# isoSPI.net
KiCad netlist of a schematic drawn in Altium Designer
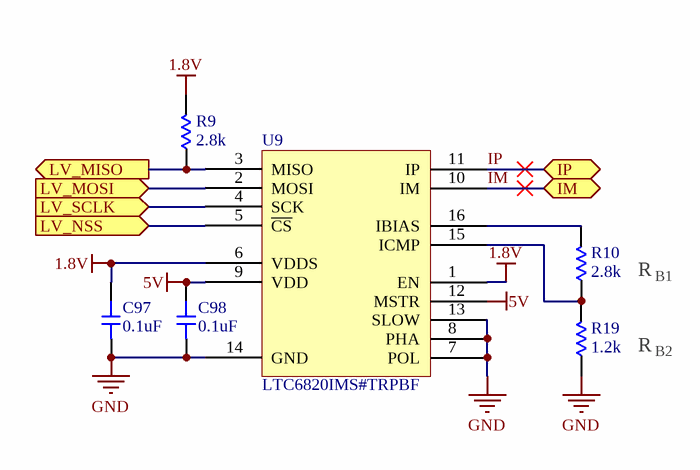
[diagram p0: isoSPI.SchDoc]

(export (version "E")
  (design (tool "Eeschema 10.0.6"))
  (components
    (comp (ref "C97")
      (value "0.1uF")
      (footprint "0603-CAP")
      (description "Capacitor")
      (libsource (lib "AMDC") (part "Capacitor"))
    )
    (comp (ref "C98")
      (value "0.1uF")
      (footprint "0603-CAP")
      (description "Capacitor")
      (libsource (lib "AMDC") (part "Capacitor"))
    )
    (comp (ref "R9")
      (value "2.8k")
      (footprint "0603-RES")
      (description "Resistor")
      (libsource (lib "AMDC") (part "Resistor"))
    )
    (comp (ref "R10")
      (value "2.8k")
      (footprint "0603-RES")
      (description "Resistor")
      (libsource (lib "AMDC") (part "Resistor"))
    )
    (comp (ref "R19")
      (value "1.2k")
      (footprint "0603-RES")
      (description "Resistor")
      (libsource (lib "AMDC") (part "Resistor"))
    )
    (comp (ref "U9")
      (value "LTC6820IMS#TRPBF")
      (footprint "TSSOP50P490X110-16N")
      (description "IC INTERFACE SPECIALIZED 16MSOP")
      (libsource (lib "AMDC") (part "LTC6820IMS#TRPBF"))
    )
  )
  (nets
    (net (code "1") (name "/IM") (class "Default")
      (node (ref "U9") (pin "10") (pinfunction "IM_10") (pintype "passive"))
    )
    (net (code "2") (name "/IP") (class "Default")
      (node (ref "U9") (pin "11") (pinfunction "IP_11") (pintype "passive"))
    )
    (net (code "3") (name "/LV_MISO") (class "Default")
      (node (ref "R9") (pin "1") (pinfunction "1_1") (pintype "passive"))
      (node (ref "U9") (pin "3") (pinfunction "MISO_3") (pintype "passive"))
    )
    (net (code "4") (name "/LV_MOSI") (class "Default")
      (node (ref "U9") (pin "2") (pinfunction "MOSI_2") (pintype "passive"))
    )
    (net (code "5") (name "/LV_NSS") (class "Default")
      (node (ref "U9") (pin "5") (pinfunction "~{CS}_5") (pintype "passive"))
    )
    (net (code "6") (name "/LV_SCLK") (class "Default")
      (node (ref "U9") (pin "4") (pinfunction "SCK_4") (pintype "passive"))
    )
    (net (code "7") (name "1.8V") (class "Default")
      (node (ref "C97") (pin "2") (pinfunction "2_2") (pintype "passive"))
      (node (ref "R9") (pin "2") (pinfunction "2_2") (pintype "passive"))
      (node (ref "U9") (pin "1") (pinfunction "EN_1") (pintype "passive"))
      (node (ref "U9") (pin "6") (pinfunction "VDDS_6") (pintype "passive"))
    )
    (net (code "8") (name "5V") (class "Default")
      (node (ref "C98") (pin "2") (pinfunction "2_2") (pintype "passive"))
      (node (ref "U9") (pin "12") (pinfunction "MSTR_12") (pintype "passive"))
      (node (ref "U9") (pin "9") (pinfunction "VDD_9") (pintype "passive"))
    )
    (net (code "9") (name "GND") (class "Default")
      (node (ref "C97") (pin "1") (pinfunction "1_1") (pintype "passive"))
      (node (ref "C98") (pin "1") (pinfunction "1_1") (pintype "passive"))
      (node (ref "R19") (pin "1") (pinfunction "1_1") (pintype "passive"))
      (node (ref "U9") (pin "13") (pinfunction "SLOW_13") (pintype "passive"))
      (node (ref "U9") (pin "14") (pinfunction "GND_14") (pintype "passive"))
      (node (ref "U9") (pin "7") (pinfunction "POL_7") (pintype "passive"))
      (node (ref "U9") (pin "8") (pinfunction "PHA_8") (pintype "passive"))
    )
    (net (code "10") (name "Net-(U9-IBIAS)") (class "Default")
      (node (ref "R10") (pin "2") (pinfunction "2_2") (pintype "passive"))
      (node (ref "U9") (pin "16") (pinfunction "IBIAS_16") (pintype "passive"))
    )
    (net (code "11") (name "Net-(U9-ICMP)") (class "Default")
      (node (ref "R10") (pin "1") (pinfunction "1_1") (pintype "passive"))
      (node (ref "R19") (pin "2") (pinfunction "2_2") (pintype "passive"))
      (node (ref "U9") (pin "15") (pinfunction "ICMP_15") (pintype "passive"))
    )
  )
)
